# USB.net
KiCad netlist of a schematic drawn in Altium Designer
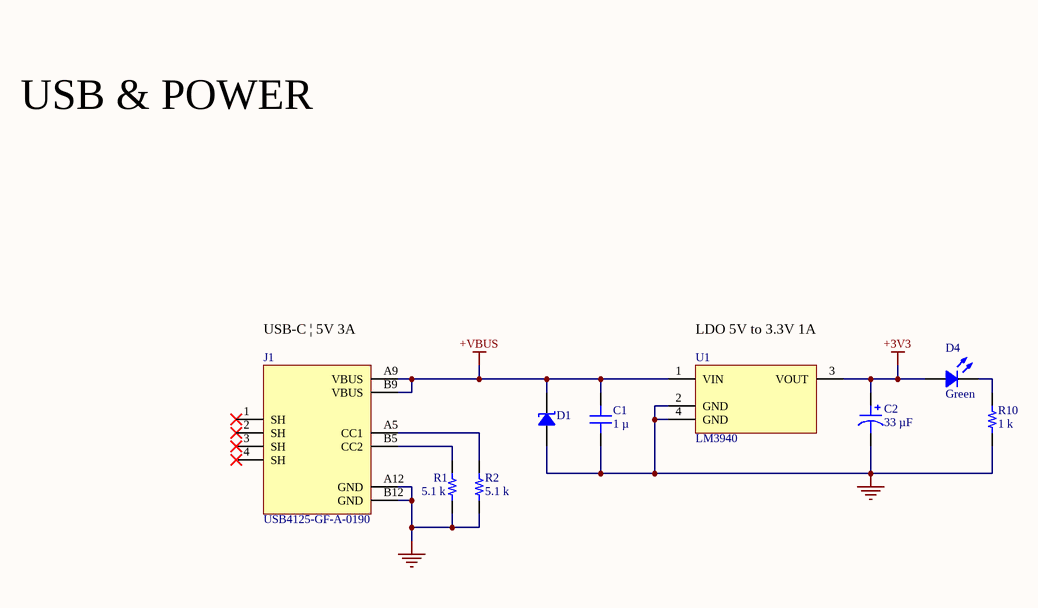
[diagram p0: USB.SchDoc]

(export (version "E")
  (design (tool "Eeschema 10.0.6"))
  (components
    (comp (ref "C1")
      (value "1 µ")
      (footprint "CAP 0603_1608")
      (description "CAP CER 1UF 16V X7R 0603")
      (fields (field (name "PART NUMBER") "C0603C105K4RACAUTO") (field (name "MANUFACTURER") "KEMET"))
      (libsource (lib "Celestial Altium Library - altium_library") (part "Capacitor"))
    )
    (comp (ref "C2")
      (value "33 µF")
      (footprint "CAP POL 1411_3528")
      (description "CAP TANT 33UF 20% 16V 1411")
      (fields (field (name "PART NUMBER") "T495B336M016ATE350") (field (name "MANUFACTURER") "KEMET"))
      (libsource (lib "Celestial Altium Library - altium_library") (part "Polarised Capacitor"))
    )
    (comp (ref "D1")
      (value "VTVS5V0ASMF-M3-08")
      (footprint "SMF DO-219AB")
      (description "TVS DIODE 5V 8.9V DO219AB")
      (fields (field (name "MANUFACTURER") "Vishay Semiconductor Diodes Division"))
      (libsource (lib "Celestial Altium Library - altium_library") (part "DIODE TVS UNI"))
    )
    (comp (ref "D4")
      (value "Green")
      (footprint "LED 0603_1608 GREEN")
      (description "LED GREEN CLEAR SMD")
      (fields
        (field (name "PART NUMBER") "SML-LXFP0603SUGCTR")
        (field (name "MANUFACTURER") "Lumex Opto/Components Inc.")
      )
      (libsource (lib "Celestial Altium Library - altium_library") (part "LED"))
    )
    (comp (ref "J1")
      (value "USB4125-GF-A-0190")
      (footprint "FP-USB4125-GF-A-0190-MFG")
      (fields (field (name "MANUFACTURER PART #") "USB4125-GF-A"))
      (libsource (lib "University of South Florida") (part "USB4125-GF-A-0190"))
    )
    (comp (ref "R1")
      (value "5.1 k")
      (footprint "RES 0603_1608")
      (description "RES 5.1K OHM 5% 1/10W 0603")
      (fields
        (field (name "PART NUMBER") "RMCF0603JG5K10")
        (field (name "MANUFACTURER") "Stackpole Electronics Inc")
      )
      (libsource (lib "Celestial Altium Library - altium_library") (part "Resistor"))
    )
    (comp (ref "R2")
      (value "5.1 k")
      (footprint "RES 0603_1608")
      (description "RES 5.1K OHM 5% 1/10W 0603")
      (fields
        (field (name "PART NUMBER") "RMCF0603JG5K10")
        (field (name "MANUFACTURER") "Stackpole Electronics Inc")
      )
      (libsource (lib "Celestial Altium Library - altium_library") (part "Resistor"))
    )
    (comp (ref "R10")
      (value "1 k")
      (footprint "RES 0603_1608")
      (description "RES SMD 1K OHM 0.1% 1/16W 0603")
      (fields
        (field (name "PART NUMBER") "CPF0603B1K0E")
        (field (name "MANUFACTURER") "TE Connectivity Passive Product")
      )
      (libsource (lib "Celestial Altium Library - altium_library") (part "Resistor"))
    )
    (comp (ref "U1")
      (value "LM3940")
      (footprint "FP-DCY0004A-IPC_C")
      (description "IC REG LDO 3.3V 1A SOT223")
      (libsource (lib "University of South Florida") (part "LM3940IMP-3.3/NOPB"))
    )
  )
  (nets
    (net (code "1") (name "+3V3") (class "Default")
      (node (ref "C2") (pin "1") (pinfunction "1_1") (pintype "passive"))
      (node (ref "D4") (pin "1") (pinfunction "1_1") (pintype "passive"))
      (node (ref "U1") (pin "3") (pinfunction "VOUT_3") (pintype "power_in"))
    )
    (net (code "2") (name "+VBUS") (class "Default")
      (node (ref "C1") (pin "2") (pinfunction "2_2") (pintype "passive"))
      (node (ref "D1") (pin "2") (pinfunction "2_2") (pintype "passive"))
      (node (ref "J1") (pin "A9") (pinfunction "VBUS_A9") (pintype "power_in"))
      (node (ref "J1") (pin "B9") (pinfunction "VBUS_B9") (pintype "power_in"))
      (node (ref "U1") (pin "1") (pinfunction "VIN_1") (pintype "power_in"))
    )
    (net (code "3") (name "GND") (class "Default")
      (node (ref "C1") (pin "1") (pinfunction "1_1") (pintype "passive"))
      (node (ref "C2") (pin "2") (pinfunction "2_2") (pintype "passive"))
      (node (ref "D1") (pin "1") (pinfunction "1_1") (pintype "passive"))
      (node (ref "J1") (pin "A12") (pinfunction "GND_A12") (pintype "passive"))
      (node (ref "J1") (pin "B12") (pinfunction "GND_B12") (pintype "passive"))
      (node (ref "R1") (pin "1") (pinfunction "1_1") (pintype "passive"))
      (node (ref "R10") (pin "2") (pinfunction "2_2") (pintype "passive"))
      (node (ref "R2") (pin "1") (pinfunction "1_1") (pintype "passive"))
      (node (ref "U1") (pin "2") (pinfunction "GND_2") (pintype "power_in"))
      (node (ref "U1") (pin "4") (pinfunction "GND_4") (pintype "power_in"))
    )
    (net (code "4") (name "Net-(D4-Pad2)") (class "Default")
      (node (ref "D4") (pin "2") (pinfunction "2_2") (pintype "passive"))
      (node (ref "R10") (pin "1") (pinfunction "1_1") (pintype "passive"))
    )
    (net (code "5") (name "Net-(J1-CC1)") (class "Default")
      (node (ref "J1") (pin "A5") (pinfunction "CC1_A5") (pintype "passive"))
      (node (ref "R2") (pin "2") (pinfunction "2_2") (pintype "passive"))
    )
    (net (code "6") (name "Net-(J1-CC2)") (class "Default")
      (node (ref "J1") (pin "B5") (pinfunction "CC2_B5") (pintype "passive"))
      (node (ref "R1") (pin "2") (pinfunction "2_2") (pintype "passive"))
    )
    (net (code "7") (name "unconnected-(J1-SH-Pad1)") (class "Default")
      (node (ref "J1") (pin "1") (pinfunction "SH_1") (pintype "passive+no_connect"))
    )
    (net (code "8") (name "unconnected-(J1-SH-Pad2)") (class "Default")
      (node (ref "J1") (pin "2") (pinfunction "SH_2") (pintype "passive+no_connect"))
    )
    (net (code "9") (name "unconnected-(J1-SH-Pad3)") (class "Default")
      (node (ref "J1") (pin "3") (pinfunction "SH_3") (pintype "passive+no_connect"))
    )
    (net (code "10") (name "unconnected-(J1-SH-Pad4)") (class "Default")
      (node (ref "J1") (pin "4") (pinfunction "SH_4") (pintype "passive+no_connect"))
    )
  )
)
